# IFE_POWER_DIST_V1.net
KiCad netlist of a schematic drawn in EAGLE
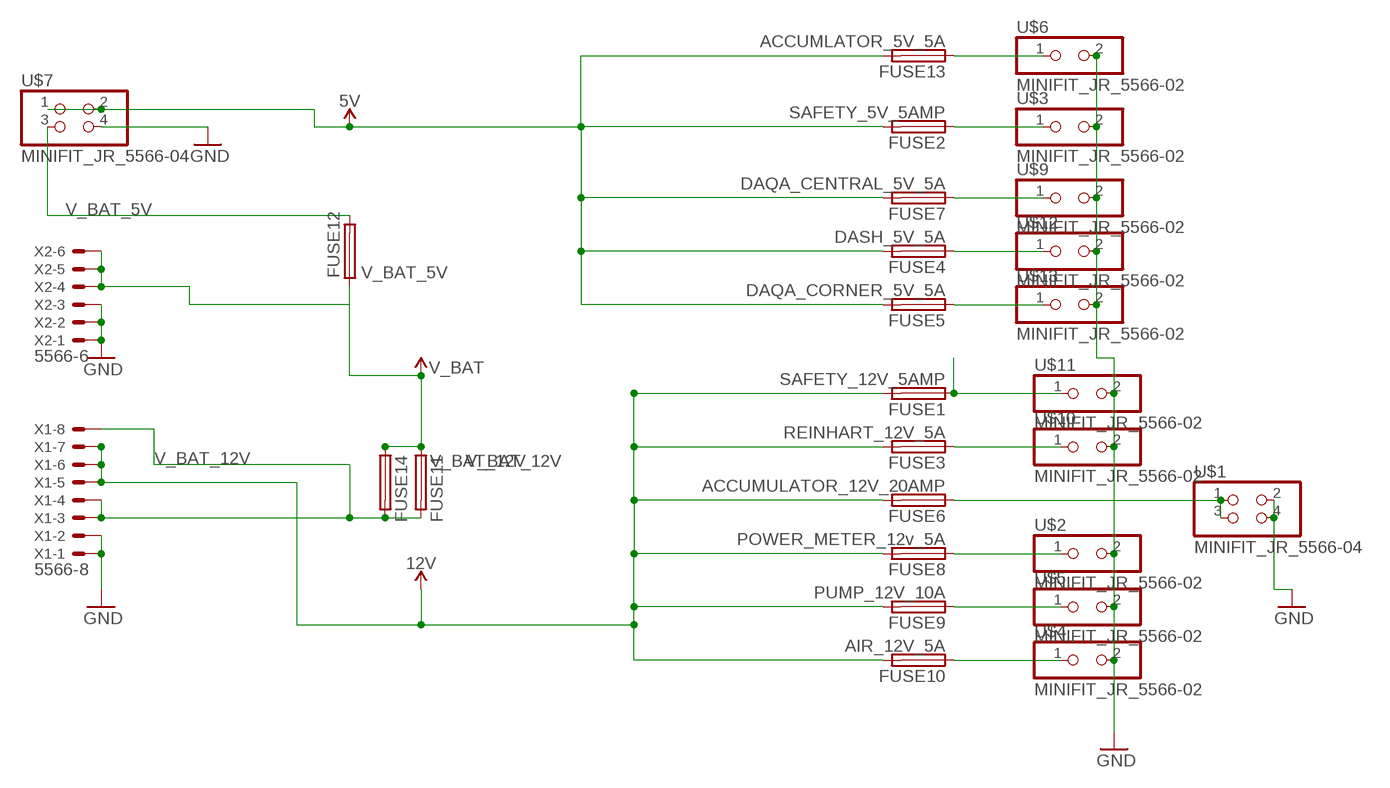
[diagram p0: schematic, sheet 1]

(export (version "E")
  (design (tool "Eeschema 10.0.6"))
  (components
    (comp (ref "FUSE1")
      (value "SAFETY_12V_5AMP")
      (footprint "eagle-import:3568")
      (libsource (lib "eagle-import") (part "MINI297-3568"))
    )
    (comp (ref "FUSE2")
      (value "SAFETY_5V_5AMP")
      (footprint "eagle-import:3568")
      (libsource (lib "eagle-import") (part "MINI297-3568"))
    )
    (comp (ref "FUSE3")
      (value "REINHART_12V_5A")
      (footprint "eagle-import:3568")
      (libsource (lib "eagle-import") (part "MINI297-3568"))
    )
    (comp (ref "FUSE4")
      (value "DASH_5V_5A")
      (footprint "eagle-import:3568")
      (libsource (lib "eagle-import") (part "MINI297-3568"))
    )
    (comp (ref "FUSE5")
      (value "DAQA_CORNER_5V_5A")
      (footprint "eagle-import:3568")
      (libsource (lib "eagle-import") (part "MINI297-3568"))
    )
    (comp (ref "FUSE6")
      (value "ACCUMULATOR_12V_20AMP")
      (footprint "eagle-import:3568")
      (libsource (lib "eagle-import") (part "MINI297-3568"))
    )
    (comp (ref "FUSE7")
      (value "DAQA_CENTRAL_5V_5A")
      (footprint "eagle-import:3568")
      (libsource (lib "eagle-import") (part "MINI297-3568"))
    )
    (comp (ref "FUSE8")
      (value "POWER_METER_12v_5A")
      (footprint "eagle-import:3568")
      (libsource (lib "eagle-import") (part "MINI297-3568"))
    )
    (comp (ref "FUSE9")
      (value "PUMP_12V_10A")
      (footprint "eagle-import:3568")
      (libsource (lib "eagle-import") (part "MINI297-3568"))
    )
    (comp (ref "FUSE10")
      (value "AIR_12V_5A")
      (footprint "eagle-import:3568")
      (libsource (lib "eagle-import") (part "MINI297-3568"))
    )
    (comp (ref "FUSE11")
      (value "V_BAT_12V")
      (footprint "eagle-import:3568")
      (libsource (lib "eagle-import") (part "MINI297-3568"))
    )
    (comp (ref "FUSE12")
      (value "V_BAT_5V")
      (footprint "eagle-import:3568")
      (libsource (lib "eagle-import") (part "MINI297-3568"))
    )
    (comp (ref "FUSE13")
      (value "ACCUMLATOR_5V_5A")
      (footprint "eagle-import:3568")
      (libsource (lib "eagle-import") (part "MINI297-3568"))
    )
    (comp (ref "FUSE14")
      (value "V_BAT_12V")
      (footprint "eagle-import:3568")
      (libsource (lib "eagle-import") (part "MINI297-3568"))
    )
    (comp (ref "U$1")
      (value "MINIFIT_JR_5566-04")
      (footprint "eagle-import:MINIFIT_JR_5566-04")
      (libsource (lib "eagle-import") (part "MINIFIT_JR_5566-04"))
    )
    (comp (ref "U$2")
      (value "MINIFIT_JR_5566-02")
      (footprint "eagle-import:MINIFIT_JR_5566-02")
      (libsource (lib "eagle-import") (part "MINIFIT_JR_5566-02"))
    )
    (comp (ref "U$3")
      (value "MINIFIT_JR_5566-02")
      (footprint "eagle-import:MINIFIT_JR_5566-02")
      (libsource (lib "eagle-import") (part "MINIFIT_JR_5566-02"))
    )
    (comp (ref "U$4")
      (value "MINIFIT_JR_5566-02")
      (footprint "eagle-import:MINIFIT_JR_5566-02")
      (libsource (lib "eagle-import") (part "MINIFIT_JR_5566-02"))
    )
    (comp (ref "U$5")
      (value "MINIFIT_JR_5566-02")
      (footprint "eagle-import:MINIFIT_JR_5566-02")
      (libsource (lib "eagle-import") (part "MINIFIT_JR_5566-02"))
    )
    (comp (ref "U$6")
      (value "MINIFIT_JR_5566-02")
      (footprint "eagle-import:MINIFIT_JR_5566-02")
      (libsource (lib "eagle-import") (part "MINIFIT_JR_5566-02"))
    )
    (comp (ref "U$7")
      (value "MINIFIT_JR_5566-04")
      (footprint "eagle-import:MINIFIT_JR_5566-04")
      (libsource (lib "eagle-import") (part "MINIFIT_JR_5566-04"))
    )
    (comp (ref "U$9")
      (value "MINIFIT_JR_5566-02")
      (footprint "eagle-import:MINIFIT_JR_5566-02")
      (libsource (lib "eagle-import") (part "MINIFIT_JR_5566-02"))
    )
    (comp (ref "U$10")
      (value "MINIFIT_JR_5566-02")
      (footprint "eagle-import:MINIFIT_JR_5566-02")
      (libsource (lib "eagle-import") (part "MINIFIT_JR_5566-02"))
    )
    (comp (ref "U$11")
      (value "MINIFIT_JR_5566-02")
      (footprint "eagle-import:MINIFIT_JR_5566-02")
      (libsource (lib "eagle-import") (part "MINIFIT_JR_5566-02"))
    )
    (comp (ref "U$12")
      (value "MINIFIT_JR_5566-02")
      (footprint "eagle-import:MINIFIT_JR_5566-02")
      (libsource (lib "eagle-import") (part "MINIFIT_JR_5566-02"))
    )
    (comp (ref "U$13")
      (value "MINIFIT_JR_5566-02")
      (footprint "eagle-import:MINIFIT_JR_5566-02")
      (libsource (lib "eagle-import") (part "MINIFIT_JR_5566-02"))
    )
    (comp (ref "X1")
      (value "5566-8")
      (footprint "eagle-import:5566-8")
      (fields (field (name "MF") "MOLEX"))
      (libsource (lib "eagle-import") (part "5566-8"))
    )
    (comp (ref "X2")
      (value "5566-6")
      (footprint "eagle-import:5566-6")
      (fields (field (name "MF") "MOLEX") (field (name "MPN") "95566-61002"))
      (libsource (lib "eagle-import") (part "5566-6"))
    )
  )
  (nets
    (net (code "1") (name "/V_BAT_5V") (class "Default")
      (node (ref "FUSE12") (pin "P$2") (pinfunction "2_P$2") (pintype "passive"))
      (node (ref "FUSE12") (pin "P$3") (pinfunction "2_P$3") (pintype "passive"))
      (node (ref "U$7") (pin "3") (pinfunction "3_3") (pintype "passive"))
    )
    (net (code "2") (name "/V_BAT_12V") (class "Default")
      (node (ref "FUSE11") (pin "P$2") (pinfunction "2_P$2") (pintype "passive"))
      (node (ref "FUSE11") (pin "P$3") (pinfunction "2_P$3") (pintype "passive"))
      (node (ref "FUSE14") (pin "P$2") (pinfunction "2_P$2") (pintype "passive"))
      (node (ref "FUSE14") (pin "P$3") (pinfunction "2_P$3") (pintype "passive"))
      (node (ref "X1") (pin "3") (pinfunction "S_3") (pintype "passive"))
      (node (ref "X1") (pin "4") (pinfunction "S_4") (pintype "passive"))
      (node (ref "X1") (pin "8") (pinfunction "S_8") (pintype "passive"))
    )
    (net (code "3") (name "5V") (class "Default")
      (node (ref "FUSE13") (pin "P$2") (pinfunction "2_P$2") (pintype "passive"))
      (node (ref "FUSE13") (pin "P$3") (pinfunction "2_P$3") (pintype "passive"))
      (node (ref "FUSE2") (pin "P$2") (pinfunction "2_P$2") (pintype "passive"))
      (node (ref "FUSE2") (pin "P$3") (pinfunction "2_P$3") (pintype "passive"))
      (node (ref "FUSE4") (pin "P$2") (pinfunction "2_P$2") (pintype "passive"))
      (node (ref "FUSE4") (pin "P$3") (pinfunction "2_P$3") (pintype "passive"))
      (node (ref "FUSE5") (pin "P$2") (pinfunction "2_P$2") (pintype "passive"))
      (node (ref "FUSE5") (pin "P$3") (pinfunction "2_P$3") (pintype "passive"))
      (node (ref "FUSE7") (pin "P$2") (pinfunction "2_P$2") (pintype "passive"))
      (node (ref "FUSE7") (pin "P$3") (pinfunction "2_P$3") (pintype "passive"))
      (node (ref "U$7") (pin "1") (pinfunction "1_1") (pintype "passive"))
      (node (ref "U$7") (pin "2") (pinfunction "2_2") (pintype "passive"))
    )
    (net (code "4") (name "12V") (class "Default")
      (node (ref "FUSE1") (pin "P$2") (pinfunction "2_P$2") (pintype "passive"))
      (node (ref "FUSE1") (pin "P$3") (pinfunction "2_P$3") (pintype "passive"))
      (node (ref "FUSE10") (pin "P$2") (pinfunction "2_P$2") (pintype "passive"))
      (node (ref "FUSE10") (pin "P$3") (pinfunction "2_P$3") (pintype "passive"))
      (node (ref "FUSE3") (pin "P$2") (pinfunction "2_P$2") (pintype "passive"))
      (node (ref "FUSE3") (pin "P$3") (pinfunction "2_P$3") (pintype "passive"))
      (node (ref "FUSE6") (pin "P$2") (pinfunction "2_P$2") (pintype "passive"))
      (node (ref "FUSE6") (pin "P$3") (pinfunction "2_P$3") (pintype "passive"))
      (node (ref "FUSE8") (pin "P$2") (pinfunction "2_P$2") (pintype "passive"))
      (node (ref "FUSE8") (pin "P$3") (pinfunction "2_P$3") (pintype "passive"))
      (node (ref "FUSE9") (pin "P$2") (pinfunction "2_P$2") (pintype "passive"))
      (node (ref "FUSE9") (pin "P$3") (pinfunction "2_P$3") (pintype "passive"))
      (node (ref "X1") (pin "5") (pinfunction "S_5") (pintype "passive"))
      (node (ref "X1") (pin "6") (pinfunction "S_6") (pintype "passive"))
      (node (ref "X1") (pin "7") (pinfunction "S_7") (pintype "passive"))
    )
    (net (code "5") (name "GND") (class "Default")
      (node (ref "U$1") (pin "2") (pinfunction "2_2") (pintype "passive"))
      (node (ref "U$1") (pin "4") (pinfunction "4_4") (pintype "passive"))
      (node (ref "U$10") (pin "2") (pinfunction "2_2") (pintype "passive"))
      (node (ref "U$11") (pin "2") (pinfunction "2_2") (pintype "passive"))
      (node (ref "U$12") (pin "2") (pinfunction "2_2") (pintype "passive"))
      (node (ref "U$13") (pin "2") (pinfunction "2_2") (pintype "passive"))
      (node (ref "U$2") (pin "2") (pinfunction "2_2") (pintype "passive"))
      (node (ref "U$3") (pin "2") (pinfunction "2_2") (pintype "passive"))
      (node (ref "U$4") (pin "2") (pinfunction "2_2") (pintype "passive"))
      (node (ref "U$5") (pin "2") (pinfunction "2_2") (pintype "passive"))
      (node (ref "U$6") (pin "2") (pinfunction "2_2") (pintype "passive"))
      (node (ref "U$7") (pin "4") (pinfunction "4_4") (pintype "passive"))
      (node (ref "U$9") (pin "2") (pinfunction "2_2") (pintype "passive"))
      (node (ref "X1") (pin "1") (pinfunction "S_1") (pintype "passive"))
      (node (ref "X1") (pin "2") (pinfunction "S_2") (pintype "passive"))
      (node (ref "X2") (pin "1") (pinfunction "S_1") (pintype "passive"))
      (node (ref "X2") (pin "2") (pinfunction "S_2") (pintype "passive"))
      (node (ref "X2") (pin "3") (pinfunction "S_3") (pintype "passive"))
    )
    (net (code "6") (name "Net-(FUSE1-1-PadP$1)") (class "Default")
      (node (ref "FUSE1") (pin "P$1") (pinfunction "1_P$1") (pintype "passive"))
      (node (ref "FUSE1") (pin "P$4") (pinfunction "1_P$4") (pintype "passive"))
      (node (ref "U$11") (pin "1") (pinfunction "1_1") (pintype "passive"))
    )
    (net (code "7") (name "Net-(FUSE2-1-PadP$1)") (class "Default")
      (node (ref "FUSE2") (pin "P$1") (pinfunction "1_P$1") (pintype "passive"))
      (node (ref "FUSE2") (pin "P$4") (pinfunction "1_P$4") (pintype "passive"))
      (node (ref "U$3") (pin "1") (pinfunction "1_1") (pintype "passive"))
    )
    (net (code "8") (name "Net-(FUSE3-1-PadP$1)") (class "Default")
      (node (ref "FUSE3") (pin "P$1") (pinfunction "1_P$1") (pintype "passive"))
      (node (ref "FUSE3") (pin "P$4") (pinfunction "1_P$4") (pintype "passive"))
      (node (ref "U$10") (pin "1") (pinfunction "1_1") (pintype "passive"))
    )
    (net (code "9") (name "Net-(FUSE4-1-PadP$1)") (class "Default")
      (node (ref "FUSE4") (pin "P$1") (pinfunction "1_P$1") (pintype "passive"))
      (node (ref "FUSE4") (pin "P$4") (pinfunction "1_P$4") (pintype "passive"))
      (node (ref "U$12") (pin "1") (pinfunction "1_1") (pintype "passive"))
    )
    (net (code "10") (name "Net-(FUSE5-1-PadP$1)") (class "Default")
      (node (ref "FUSE5") (pin "P$1") (pinfunction "1_P$1") (pintype "passive"))
      (node (ref "FUSE5") (pin "P$4") (pinfunction "1_P$4") (pintype "passive"))
      (node (ref "U$13") (pin "1") (pinfunction "1_1") (pintype "passive"))
    )
    (net (code "11") (name "Net-(FUSE6-1-PadP$1)") (class "Default")
      (node (ref "FUSE6") (pin "P$1") (pinfunction "1_P$1") (pintype "passive"))
      (node (ref "FUSE6") (pin "P$4") (pinfunction "1_P$4") (pintype "passive"))
      (node (ref "U$1") (pin "1") (pinfunction "1_1") (pintype "passive"))
      (node (ref "U$1") (pin "3") (pinfunction "3_3") (pintype "passive"))
    )
    (net (code "12") (name "Net-(FUSE7-1-PadP$1)") (class "Default")
      (node (ref "FUSE7") (pin "P$1") (pinfunction "1_P$1") (pintype "passive"))
      (node (ref "FUSE7") (pin "P$4") (pinfunction "1_P$4") (pintype "passive"))
      (node (ref "U$9") (pin "1") (pinfunction "1_1") (pintype "passive"))
    )
    (net (code "13") (name "Net-(FUSE8-1-PadP$1)") (class "Default")
      (node (ref "FUSE8") (pin "P$1") (pinfunction "1_P$1") (pintype "passive"))
      (node (ref "FUSE8") (pin "P$4") (pinfunction "1_P$4") (pintype "passive"))
      (node (ref "U$2") (pin "1") (pinfunction "1_1") (pintype "passive"))
    )
    (net (code "14") (name "Net-(FUSE9-1-PadP$1)") (class "Default")
      (node (ref "FUSE9") (pin "P$1") (pinfunction "1_P$1") (pintype "passive"))
      (node (ref "FUSE9") (pin "P$4") (pinfunction "1_P$4") (pintype "passive"))
      (node (ref "U$5") (pin "1") (pinfunction "1_1") (pintype "passive"))
    )
    (net (code "15") (name "Net-(FUSE10-1-PadP$1)") (class "Default")
      (node (ref "FUSE10") (pin "P$1") (pinfunction "1_P$1") (pintype "passive"))
      (node (ref "FUSE10") (pin "P$4") (pinfunction "1_P$4") (pintype "passive"))
      (node (ref "U$4") (pin "1") (pinfunction "1_1") (pintype "passive"))
    )
    (net (code "16") (name "Net-(FUSE13-1-PadP$1)") (class "Default")
      (node (ref "FUSE13") (pin "P$1") (pinfunction "1_P$1") (pintype "passive"))
      (node (ref "FUSE13") (pin "P$4") (pinfunction "1_P$4") (pintype "passive"))
      (node (ref "U$6") (pin "1") (pinfunction "1_1") (pintype "passive"))
    )
    (net (code "17") (name "V_BAT") (class "Default")
      (node (ref "FUSE11") (pin "P$1") (pinfunction "1_P$1") (pintype "passive"))
      (node (ref "FUSE11") (pin "P$4") (pinfunction "1_P$4") (pintype "passive"))
      (node (ref "FUSE12") (pin "P$1") (pinfunction "1_P$1") (pintype "passive"))
      (node (ref "FUSE12") (pin "P$4") (pinfunction "1_P$4") (pintype "passive"))
      (node (ref "FUSE14") (pin "P$1") (pinfunction "1_P$1") (pintype "passive"))
      (node (ref "FUSE14") (pin "P$4") (pinfunction "1_P$4") (pintype "passive"))
      (node (ref "X2") (pin "4") (pinfunction "S_4") (pintype "passive"))
      (node (ref "X2") (pin "5") (pinfunction "S_5") (pintype "passive"))
      (node (ref "X2") (pin "6") (pinfunction "S_6") (pintype "passive"))
    )
  )
)
